# Sensor_Board.net
KiCad netlist of a schematic drawn in Altium Designer
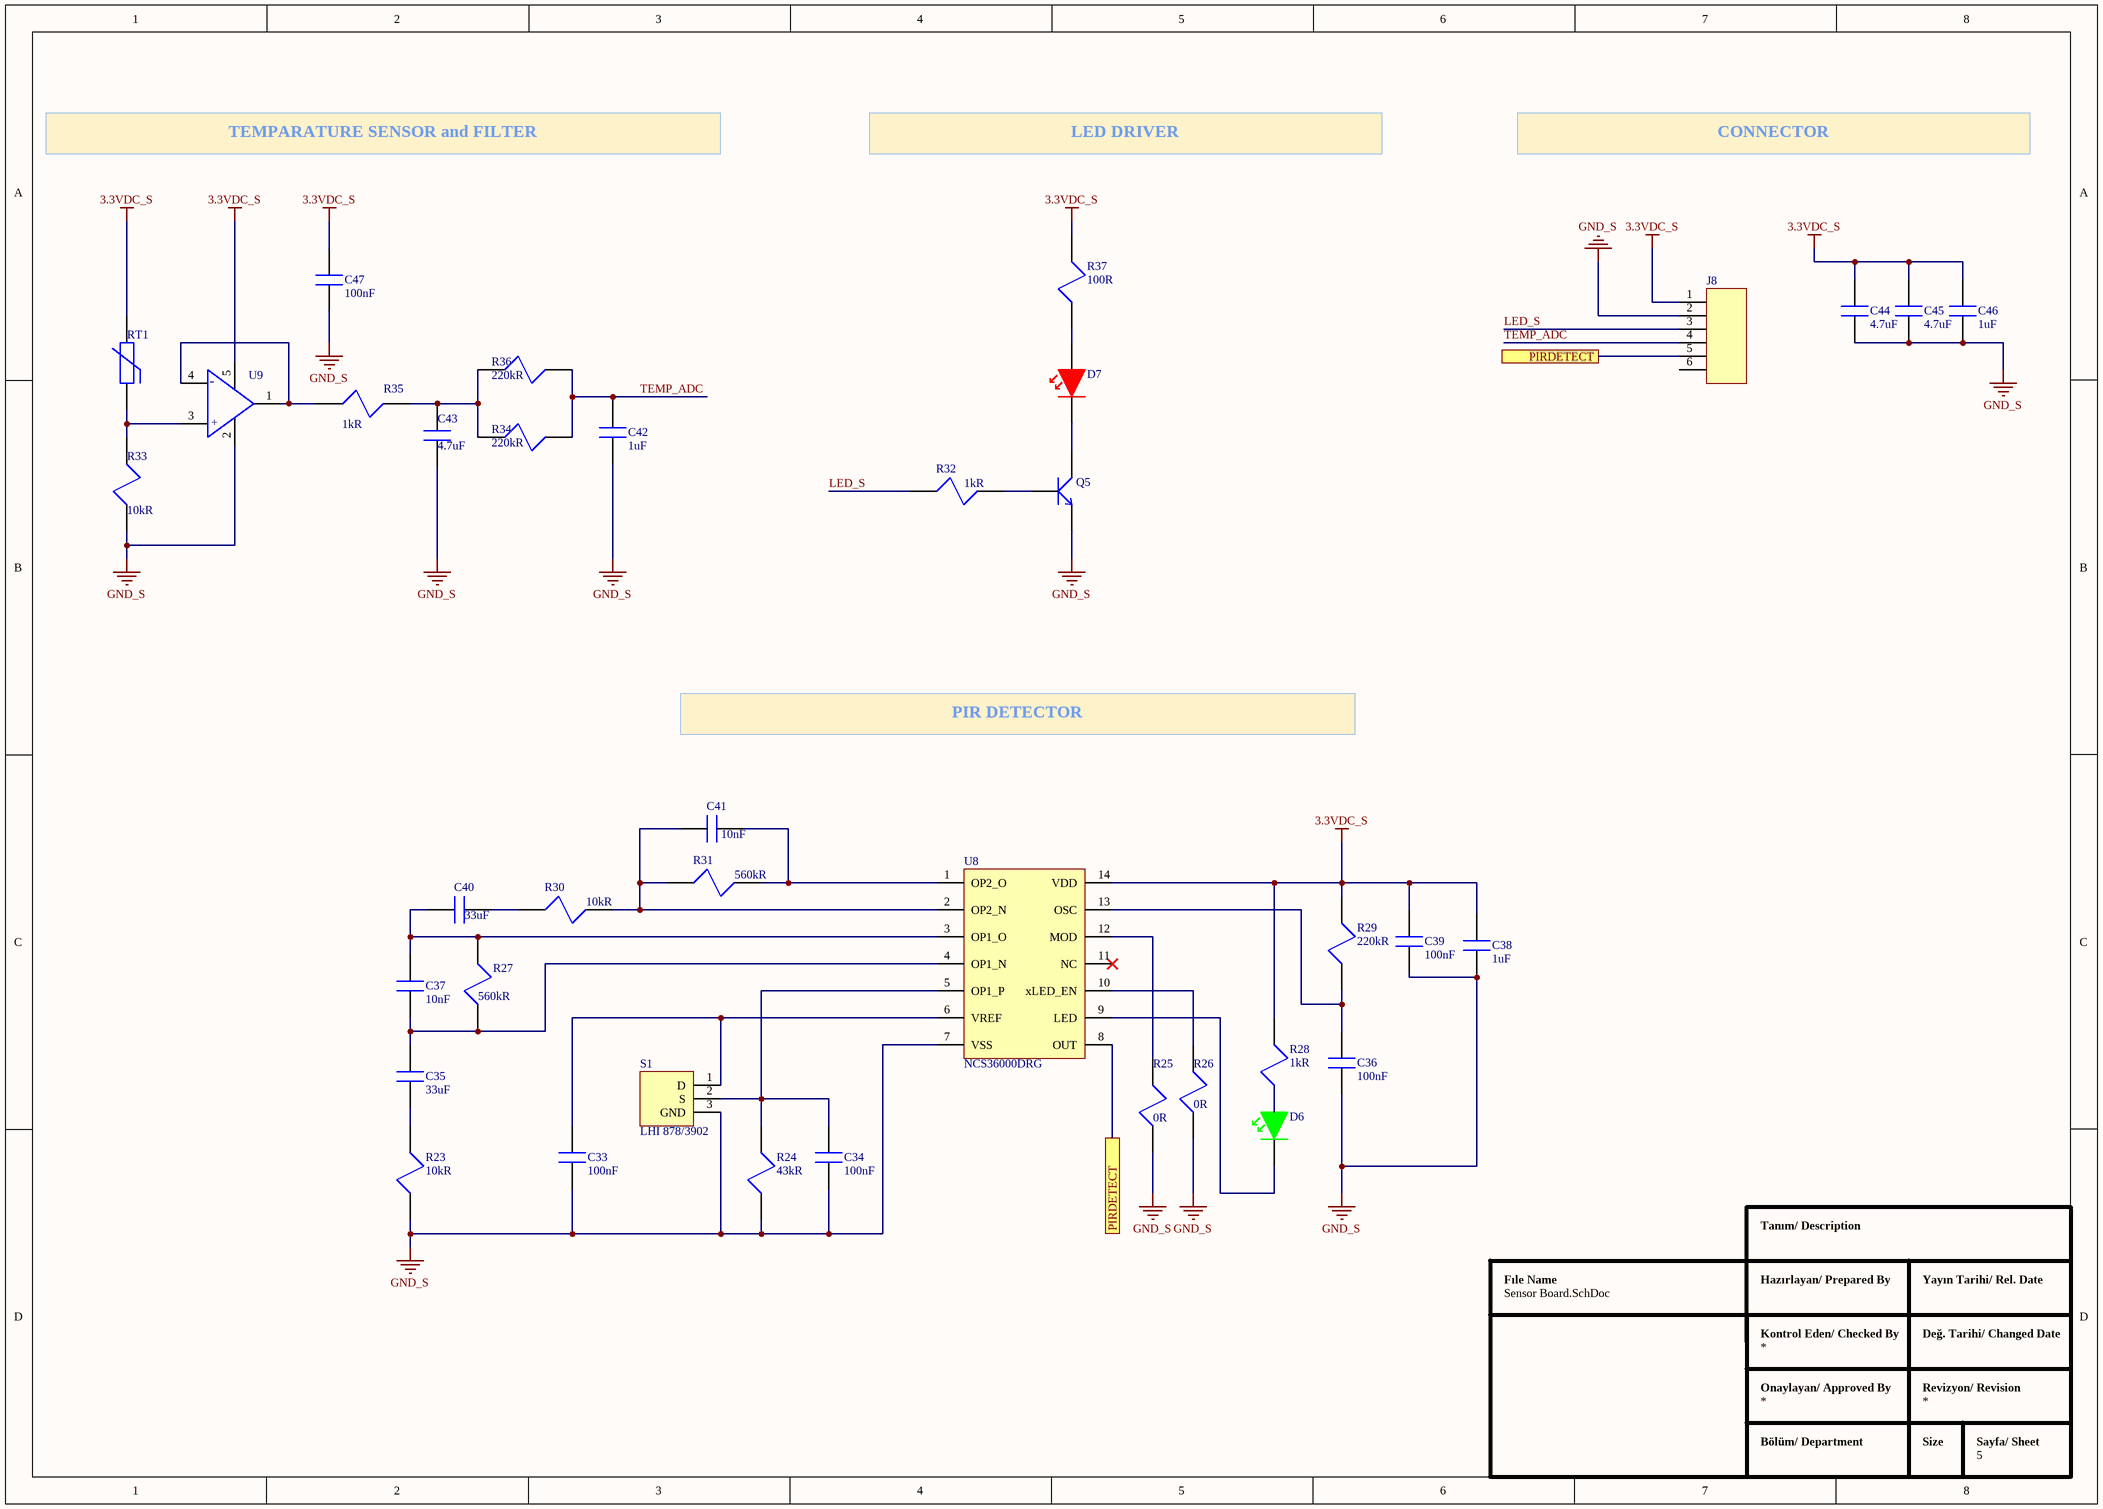
[diagram p0: Sensor Board.SchDoc]

(export (version "E")
  (design (tool "Eeschema 10.0.6"))
  (components
    (comp (ref "C33")
      (value "C0603C104M5RAC7867")
      (footprint "CAP_0603")
      (description "CAP CER 0.1UF 50V 20% X7R 0603")
      (fields
        (field (name "MANUFACTURER") "KEMET")
        (field (name "MANUFACTURER PART NUMBER") "C0603C104M5RACTU")
        (field (name "CAPACITANCE") "100nF")
        (field (name "DESIGNED BY") "Rumeysa Şahin")
      )
      (libsource (lib "Integrated_Library1") (part "CAP CER 100nF 0603"))
    )
    (comp (ref "C34")
      (value "C0603C104M5RAC7867")
      (footprint "CAP_0603")
      (description "CAP CER 0.1UF 50V 20% X7R 0603")
      (fields
        (field (name "MANUFACTURER") "KEMET")
        (field (name "MANUFACTURER PART NUMBER") "C0603C104M5RACTU")
        (field (name "CAPACITANCE") "100nF")
        (field (name "DESIGNED BY") "Rumeysa Şahin")
      )
      (libsource (lib "Integrated_Library1") (part "CAP CER 100nF 0603"))
    )
    (comp (ref "C35")
      (value "C3216X5R1E336M160AC")
      (footprint "CAP_1206")
      (description "C Series 1206 33 uF 25 V ±20 % Tolerance X5R SMT Multilayer Ceramic Capacitor")
      (fields
        (field (name "MANUFACTURER") "TDK")
        (field (name "TOLERANCE") "20%")
        (field (name "CAPACITANCE") "33uF")
        (field (name "DESIGNED BY") "Rumeysa Şahin")
      )
      (libsource (lib "Integrated_Library1") (part "CAP CER 33uF 1206"))
    )
    (comp (ref "C36")
      (value "C0603C104M5RAC7867")
      (footprint "CAP_0603")
      (description "CAP CER 0.1UF 50V 20% X7R 0603")
      (fields
        (field (name "MANUFACTURER") "KEMET")
        (field (name "MANUFACTURER PART NUMBER") "C0603C104M5RACTU")
        (field (name "CAPACITANCE") "100nF")
        (field (name "DESIGNED BY") "Rumeysa Şahin")
      )
      (libsource (lib "Integrated_Library1") (part "CAP CER 100nF 0603"))
    )
    (comp (ref "C37")
      (value "0603B103K160CT")
      (footprint "CAP_0603")
      (description "Multilayer Ceramic Capacitor, 0.01 F, 10%, X7R, 16 V, 0603 [1608 Metric] RoHS Compliant: Yes")
      (fields
        (field (name "MANUFACTURER") "Walsin Technologies")
        (field (name "TOLERANCE") "10%")
        (field (name "CAPACITANCE") "10nF")
        (field (name "DESIGNED BY") "Rumeysa Şahin")
      )
      (libsource (lib "Integrated_Library1") (part "CAP CER 10nF 0603"))
    )
    (comp (ref "C38")
      (value "CL21B105KBFNNNE")
      (footprint "CAP_0805")
      (description "CAP CER 1UF 50V X7R 0805")
      (fields
        (field (name "MANUFACTURER") "Samsung")
        (field (name "TOLERANCE") "10%")
        (field (name "CAPACITANCE") "1uF")
        (field (name "DESIGNED BY") "Rumeysa Şahin")
      )
      (libsource (lib "Integrated_Library1") (part "CAP CER 1UF 0805"))
    )
    (comp (ref "C39")
      (value "C0603C104M5RAC7867")
      (footprint "CAP_0603")
      (description "CAP CER 0.1UF 50V 20% X7R 0603")
      (fields
        (field (name "MANUFACTURER") "KEMET")
        (field (name "MANUFACTURER PART NUMBER") "C0603C104M5RACTU")
        (field (name "CAPACITANCE") "100nF")
        (field (name "DESIGNED BY") "Rumeysa Şahin")
      )
      (libsource (lib "Integrated_Library1") (part "CAP CER 100nF 0603"))
    )
    (comp (ref "C40")
      (value "C3216X5R1E336M160AC")
      (footprint "CAP_1206")
      (description "C Series 1206 33 uF 25 V ±20 % Tolerance X5R SMT Multilayer Ceramic Capacitor")
      (fields
        (field (name "MANUFACTURER") "TDK")
        (field (name "TOLERANCE") "20%")
        (field (name "CAPACITANCE") "33uF")
        (field (name "DESIGNED BY") "Rumeysa Şahin")
      )
      (libsource (lib "Integrated_Library1") (part "CAP CER 33uF 1206"))
    )
    (comp (ref "C41")
      (value "0603B103K160CT")
      (footprint "CAP_0603")
      (description "Multilayer Ceramic Capacitor, 0.01 F, 10%, X7R, 16 V, 0603 [1608 Metric] RoHS Compliant: Yes")
      (fields
        (field (name "MANUFACTURER") "Walsin Technologies")
        (field (name "TOLERANCE") "10%")
        (field (name "CAPACITANCE") "10nF")
        (field (name "DESIGNED BY") "Rumeysa Şahin")
      )
      (libsource (lib "Integrated_Library1") (part "CAP CER 10nF 0603"))
    )
    (comp (ref "C42")
      (value "CL21B105KBFNNNE")
      (footprint "CAP_0805")
      (description "CAP CER 1UF 50V X7R 0805")
      (fields
        (field (name "MANUFACTURER") "Samsung")
        (field (name "TOLERANCE") "10%")
        (field (name "CAPACITANCE") "1uF")
        (field (name "DESIGNED BY") "Rumeysa Şahin")
      )
      (libsource (lib "Integrated_Library1") (part "CAP CER 1UF 0805"))
    )
    (comp (ref "C43")
      (value "CL21A475KAQNNNE")
      (footprint "CAP_0805")
      (description "CAP CER 4.7UF 25V X5R 0805")
      (fields
        (field (name "MANUFACTURER") "Samsung")
        (field (name "TOLERANCE") "10%")
        (field (name "CAPACITANCE") "4.7uF")
        (field (name "DESIGNED BY") "Rumeysa Şahin")
      )
      (libsource (lib "Integrated_Library1") (part "CAP CER 4.7uF 0805"))
    )
    (comp (ref "C44")
      (value "CL21A475KAQNNNE")
      (footprint "CAP_0805")
      (description "CAP CER 4.7UF 25V X5R 0805")
      (fields
        (field (name "MANUFACTURER") "Samsung")
        (field (name "TOLERANCE") "10%")
        (field (name "CAPACITANCE") "4.7uF")
        (field (name "DESIGNED BY") "Rumeysa Şahin")
      )
      (libsource (lib "Integrated_Library1") (part "CAP CER 4.7uF 0805"))
    )
    (comp (ref "C45")
      (value "CL21A475KAQNNNE")
      (footprint "CAP_0805")
      (description "CAP CER 4.7UF 25V X5R 0805")
      (fields
        (field (name "MANUFACTURER") "Samsung")
        (field (name "TOLERANCE") "10%")
        (field (name "CAPACITANCE") "4.7uF")
        (field (name "DESIGNED BY") "Rumeysa Şahin")
      )
      (libsource (lib "Integrated_Library1") (part "CAP CER 4.7uF 0805"))
    )
    (comp (ref "C46")
      (value "CL21B105KBFNNNE")
      (footprint "CAP_0805")
      (description "CAP CER 1UF 50V X7R 0805")
      (fields
        (field (name "MANUFACTURER") "Samsung")
        (field (name "TOLERANCE") "10%")
        (field (name "CAPACITANCE") "1uF")
        (field (name "DESIGNED BY") "Rumeysa Şahin")
      )
      (libsource (lib "Integrated_Library1") (part "CAP CER 1UF 0805"))
    )
    (comp (ref "C47")
      (value "C0603C104M5RAC7867")
      (footprint "CAP_0603")
      (description "CAP CER 0.1UF 50V 20% X7R 0603")
      (fields
        (field (name "MANUFACTURER") "KEMET")
        (field (name "MANUFACTURER PART NUMBER") "C0603C104M5RACTU")
        (field (name "CAPACITANCE") "100nF")
        (field (name "DESIGNED BY") "Rumeysa Şahin")
      )
      (libsource (lib "Integrated_Library1") (part "CAP CER 100nF 0603"))
    )
    (comp (ref "D6")
      (value "LTST-C171GKT")
      (footprint "LED_GREEN_0805")
      (description "Green 569nm LED Indication - Discrete 2.1V 0805 (2012 Metric)")
      (fields
        (field (name "MANUFACTURER") "Osram Opto")
        (field (name "MANUFACTURER PART NUMBER") "LH R974-LP-1")
        (field (name "DESIGNED BY") "Rumeysa Şahin")
      )
      (libsource (lib "Integrated_Library1") (part "LED GREEN 0805"))
    )
    (comp (ref "D7")
      (value "LH R974-LP-1")
      (footprint "LED_RED_0805")
      (description "LED Uni-Color Hyper Red 660nm 2-Pin Chip 0805(2012Metric) T/R")
      (fields (field (name "MANUFACTURER") "Osram Opto") (field (name "DESIGNED BY") "Rumeysa Şahin"))
      (libsource (lib "Integrated_Library1") (part "LED RED 0805"))
    )
    (comp (ref "J8")
      (value "64800611622")
      (footprint "64800611622")
      (description "Conn, Header, 6POS, 1ROW, 1.5MM;")
      (fields (field (name "MANUFACTURER") "Wurth Electronics") (field (name "DESIGNED BY") "Rumeysa Şahin"))
      (libsource (lib "Integrated_Library1") (part "64800611622_CONN_6PIN"))
    )
    (comp (ref "Q5")
      (value "MMBT3904-7-F")
      (footprint "SOT23F")
      (description "NPN Ic=200mA Vceo=40V hfe=100~300 fT=310MHz P=300mW SOT-23")
      (fields (field (name "MANUFACTURER") "Diodes Zetex") (field (name "DESIGNED BY") "Rumeysa Şahin"))
      (libsource (lib "Integrated_Library1") (part "MMBT3904-7-F"))
    )
    (comp (ref "R23")
      (value "RC0603DR-0710KL")
      (footprint "RES_0603")
      (description "Res Thick Film 0603 10K Ohm 0.5% 1/10W ±100ppm/°C Molded SMD Paper T/R")
      (fields
        (field (name "MANUFACTURER") "Yageo")
        (field (name "TOLERANCE") "0.5%")
        (field (name "RESISTANCE") "10kR")
        (field (name "DESIGNED BY") "Rumeysa Şahin")
      )
      (libsource (lib "Integrated_Library1") (part "RES 10K OHM 0603"))
    )
    (comp (ref "R24")
      (value "RC0603JR-0743KL")
      (footprint "RES_0603")
      (description "Res Thick Film 0603 43K Ohm 5% 0.1W(1/10W) ±100ppm/°C Pad SMD T/R")
      (fields
        (field (name "MANUFACTURER") "Yageo")
        (field (name "TOLERANCE") "5%")
        (field (name "RESISTANCE") "43kR")
        (field (name "DESIGNED BY") "Rumeysa Şahin")
      )
      (libsource (lib "Integrated_Library1") (part "RES 43K OHM 0603"))
    )
    (comp (ref "R25")
      (value "RC0603JR-070RL")
      (footprint "RES_0603")
      (description "RES SMD 0 OHM JUMPER 1/10W 0603")
      (fields
        (field (name "MANUFACTURER") "Yageo")
        (field (name "TOLERANCE") "1%")
        (field (name "RESISTANCE") "0R")
        (field (name "DESIGNED BY") "Rumeysa Şahin")
      )
      (libsource (lib "Integrated_Library1") (part "RES 0 OHM 0603"))
    )
    (comp (ref "R26")
      (value "RC0603JR-070RL")
      (footprint "RES_0603")
      (description "RES SMD 0 OHM JUMPER 1/10W 0603")
      (fields
        (field (name "MANUFACTURER") "Yageo")
        (field (name "TOLERANCE") "1%")
        (field (name "RESISTANCE") "0R")
        (field (name "DESIGNED BY") "Rumeysa Şahin")
      )
      (libsource (lib "Integrated_Library1") (part "RES 0 OHM 0603"))
    )
    (comp (ref "R27")
      (value "RC0603JR-07560KL")
      (footprint "RES_0603")
      (description "Res Thick Film 0603 560K Ohm 5% 0.1W(1/10W) ±100ppm/C Molded SMD Paper T/R")
      (fields
        (field (name "MANUFACTURER") "Yageo")
        (field (name "TOLERANCE") "5%")
        (field (name "RESISTANCE") "560kR")
        (field (name "DESIGNED BY") "Rumeysa Şahin")
      )
      (libsource (lib "Integrated_Library1") (part "RES 560K OHM 0603"))
    )
    (comp (ref "R28")
      (value "RC0603FR-071KL")
      (footprint "RES_0603")
      (description "Res Thick Film 0603 1K Ohm 1% 1/10W ±100ppm/°C Molded SMD SMD Paper T/R")
      (fields
        (field (name "MANUFACTURER") "Yageo")
        (field (name "TOLERANCE") "1%")
        (field (name "RESISTANCE") "1kR")
        (field (name "DESIGNED BY") "Rumeysa Şahin")
      )
      (libsource (lib "Integrated_Library1") (part "RES 1K OHM 0603"))
    )
    (comp (ref "R29")
      (value "RC0603JR-07220KL")
      (footprint "RES_0603")
      (description "Res Thick Film 0603 220K Ohm 5% 0.1W(1/10W) ±100ppm/C Pad SMD T/R")
      (fields
        (field (name "MANUFACTURER") "Yageo")
        (field (name "TOLERANCE") "5%")
        (field (name "RESISTANCE") "220kR")
        (field (name "DESIGNED BY") "Rumeysa Şahin")
      )
      (libsource (lib "Integrated_Library1") (part "RES 220K OHM 0603"))
    )
    (comp (ref "R30")
      (value "RC0603DR-0710KL")
      (footprint "RES_0603")
      (description "Res Thick Film 0603 10K Ohm 0.5% 1/10W ±100ppm/°C Molded SMD Paper T/R")
      (fields
        (field (name "MANUFACTURER") "Yageo")
        (field (name "TOLERANCE") "0.5%")
        (field (name "RESISTANCE") "10kR")
        (field (name "DESIGNED BY") "Rumeysa Şahin")
      )
      (libsource (lib "Integrated_Library1") (part "RES 10K OHM 0603"))
    )
    (comp (ref "R31")
      (value "RC0603JR-07560KL")
      (footprint "RES_0603")
      (description "Res Thick Film 0603 560K Ohm 5% 0.1W(1/10W) ±100ppm/C Molded SMD Paper T/R")
      (fields
        (field (name "MANUFACTURER") "Yageo")
        (field (name "TOLERANCE") "5%")
        (field (name "RESISTANCE") "560kR")
        (field (name "DESIGNED BY") "Rumeysa Şahin")
      )
      (libsource (lib "Integrated_Library1") (part "RES 560K OHM 0603"))
    )
    (comp (ref "R32")
      (value "RC0603FR-071KL")
      (footprint "RES_0603")
      (description "Res Thick Film 0603 1K Ohm 1% 1/10W ±100ppm/°C Molded SMD SMD Paper T/R")
      (fields
        (field (name "MANUFACTURER") "Yageo")
        (field (name "TOLERANCE") "1%")
        (field (name "RESISTANCE") "1kR")
        (field (name "DESIGNED BY") "Rumeysa Şahin")
      )
      (libsource (lib "Integrated_Library1") (part "RES 1K OHM 0603"))
    )
    (comp (ref "R33")
      (value "RC0603DR-0710KL")
      (footprint "RES_0603")
      (description "Res Thick Film 0603 10K Ohm 0.5% 1/10W ±100ppm/°C Molded SMD Paper T/R")
      (fields
        (field (name "MANUFACTURER") "Yageo")
        (field (name "TOLERANCE") "0.5%")
        (field (name "RESISTANCE") "10kR")
        (field (name "DESIGNED BY") "Rumeysa Şahin")
      )
      (libsource (lib "Integrated_Library1") (part "RES 10K OHM 0603"))
    )
    (comp (ref "R34")
      (value "RC0603JR-07220KL")
      (footprint "RES_0603")
      (description "Res Thick Film 0603 220K Ohm 5% 0.1W(1/10W) ±100ppm/C Pad SMD T/R")
      (fields
        (field (name "MANUFACTURER") "Yageo")
        (field (name "TOLERANCE") "5%")
        (field (name "RESISTANCE") "220kR")
        (field (name "DESIGNED BY") "Rumeysa Şahin")
      )
      (libsource (lib "Integrated_Library1") (part "RES 220K OHM 0603"))
    )
    (comp (ref "R35")
      (value "RC0603FR-071KL")
      (footprint "RES_0603")
      (description "Res Thick Film 0603 1K Ohm 1% 1/10W ±100ppm/°C Molded SMD SMD Paper T/R")
      (fields
        (field (name "MANUFACTURER") "Yageo")
        (field (name "TOLERANCE") "1%")
        (field (name "RESISTANCE") "1kR")
        (field (name "DESIGNED BY") "Rumeysa Şahin")
      )
      (libsource (lib "Integrated_Library1") (part "RES 1K OHM 0603"))
    )
    (comp (ref "R36")
      (value "RC0603JR-07220KL")
      (footprint "RES_0603")
      (description "Res Thick Film 0603 220K Ohm 5% 0.1W(1/10W) ±100ppm/C Pad SMD T/R")
      (fields
        (field (name "MANUFACTURER") "Yageo")
        (field (name "TOLERANCE") "5%")
        (field (name "RESISTANCE") "220kR")
        (field (name "DESIGNED BY") "Rumeysa Şahin")
      )
      (libsource (lib "Integrated_Library1") (part "RES 220K OHM 0603"))
    )
    (comp (ref "R37")
      (value "RC0603JR-13100RL")
      (footprint "RES_0603")
      (description "Res Thick Film 0603 100 Ohm 5% 0.1W(1/10W) ±100ppm/C Pad SMD T/R")
      (fields
        (field (name "MANUFACTURER") "Yageo")
        (field (name "TOLERANCE") "5%")
        (field (name "RESISTANCE") "100R")
        (field (name "DESIGNED BY") "Rumeysa Şahin")
      )
      (libsource (lib "Integrated_Library1") (part "RES 100 OHM 0603"))
    )
    (comp (ref "RT1")
      (value "TFPT1206L1002FM")
      (footprint "TFPT1206L1002FM")
      (description "Thermistor PTC 10K Ohm 1% 2-Pin 1206 Surface Mount Solder Pad T/R Automotive")
      (fields
        (field (name "MANUFACTURER") "Vishay Dale")
        (field (name "TOLERANCE") "1%")
        (field (name "DESIGNED BY") "Rumeysa Şahin")
      )
      (libsource (lib "Integrated_Library1") (part "TFPT1206L1002FM"))
    )
    (comp (ref "S1")
      (value "LHI 878/3902")
      (footprint "LHI 878/3902")
      (description "Pyro Detector Dual, Motion Sens")
      (fields
        (field (name "MANUFACTURER") "Excelitas")
        (field (name "MANUFACTURER PART NUMBER") "PYD1388/7083")
        (field (name "DESIGNED BY") "Rumeysa Şahin")
      )
      (libsource (lib "Integrated_Library1") (part "LHI 878/3902"))
    )
    (comp (ref "U8")
      (value "NCS36000DRG")
      (footprint "SOIC14")
      (description "NCS36000 Series Single 5.75V Passive Infrared Detector Controller (PIR) -SOIC-14")
      (fields (field (name "MANUFACTURER") "ON Semiconductor") (field (name "DESIGNED BY") "Rumeysa Şahin"))
      (libsource (lib "Integrated_Library1") (part "NCS36000"))
    )
    (comp (ref "U9")
      (value "OPA314AIDBVR")
      (footprint "SOT23-5")
      (description "IC OPAMP GP 3MHZ RRO SOT23-5")
      (fields (field (name "MANUFACTURER") "Texas Instruments") (field (name "DESIGNED BY") "Ruemysa Şahin"))
      (libsource (lib "Integrated_Library1") (part "OPA314"))
    )
  )
  (nets
    (net (code "1") (name "/LED_S") (class "Default")
      (node (ref "J8") (pin "3") (pintype "power_in"))
      (node (ref "R32") (pin "1") (pintype "passive"))
    )
    (net (code "2") (name "/PIRDETECT") (class "Default")
      (node (ref "J8") (pin "5") (pintype "power_in"))
      (node (ref "U8") (pin "8") (pinfunction "OUT_8") (pintype "passive"))
    )
    (net (code "3") (name "/TEMP_ADC") (class "Default")
      (node (ref "C42") (pin "2") (pinfunction "2_2") (pintype "passive"))
      (node (ref "J8") (pin "4") (pintype "power_in"))
      (node (ref "R34") (pin "2") (pinfunction "2_2") (pintype "passive"))
      (node (ref "R36") (pin "2") (pinfunction "2_2") (pintype "passive"))
    )
    (net (code "4") (name "3.3VDC_S") (class "Default")
      (node (ref "C38") (pin "2") (pinfunction "2_2") (pintype "passive"))
      (node (ref "C39") (pin "2") (pinfunction "2_2") (pintype "passive"))
      (node (ref "C44") (pin "2") (pinfunction "2_2") (pintype "passive"))
      (node (ref "C45") (pin "2") (pinfunction "2_2") (pintype "passive"))
      (node (ref "C46") (pin "2") (pinfunction "2_2") (pintype "passive"))
      (node (ref "C47") (pin "2") (pinfunction "2_2") (pintype "passive"))
      (node (ref "J8") (pin "1") (pintype "power_in"))
      (node (ref "R28") (pin "2") (pinfunction "2_2") (pintype "passive"))
      (node (ref "R29") (pin "2") (pinfunction "2_2") (pintype "passive"))
      (node (ref "R37") (pin "2") (pinfunction "2_2") (pintype "passive"))
      (node (ref "RT1") (pin "2") (pinfunction "2_2") (pintype "passive"))
      (node (ref "U8") (pin "14") (pinfunction "VDD_14") (pintype "passive"))
      (node (ref "U9") (pin "5") (pinfunction "5_5") (pintype "passive"))
    )
    (net (code "5") (name "GND_S") (class "Default")
      (node (ref "C33") (pin "1") (pinfunction "1_1") (pintype "passive"))
      (node (ref "C34") (pin "1") (pinfunction "1_1") (pintype "passive"))
      (node (ref "C36") (pin "1") (pinfunction "1_1") (pintype "passive"))
      (node (ref "C38") (pin "1") (pinfunction "1_1") (pintype "passive"))
      (node (ref "C39") (pin "1") (pinfunction "1_1") (pintype "passive"))
      (node (ref "C42") (pin "1") (pinfunction "1_1") (pintype "passive"))
      (node (ref "C43") (pin "1") (pinfunction "1_1") (pintype "passive"))
      (node (ref "C44") (pin "1") (pinfunction "1_1") (pintype "passive"))
      (node (ref "C45") (pin "1") (pinfunction "1_1") (pintype "passive"))
      (node (ref "C46") (pin "1") (pinfunction "1_1") (pintype "passive"))
      (node (ref "C47") (pin "1") (pinfunction "1_1") (pintype "passive"))
      (node (ref "J8") (pin "2") (pintype "power_in"))
      (node (ref "Q5") (pin "2") (pinfunction "E_2") (pintype "power_in"))
      (node (ref "R23") (pin "1") (pintype "passive"))
      (node (ref "R24") (pin "1") (pintype "passive"))
      (node (ref "R25") (pin "1") (pintype "passive"))
      (node (ref "R26") (pin "1") (pintype "passive"))
      (node (ref "R33") (pin "2") (pinfunction "2_2") (pintype "passive"))
      (node (ref "S1") (pin "3") (pinfunction "GND_3") (pintype "passive"))
      (node (ref "U8") (pin "7") (pinfunction "VSS_7") (pintype "passive"))
      (node (ref "U9") (pin "2") (pinfunction "2_2") (pintype "passive"))
    )
    (net (code "6") (name "Net-(C35-Pad1)") (class "Default")
      (node (ref "C35") (pin "1") (pinfunction "1_1") (pintype "passive"))
      (node (ref "R23") (pin "2") (pinfunction "2_2") (pintype "passive"))
    )
    (net (code "7") (name "Net-(C40-Pad2)") (class "Default")
      (node (ref "C40") (pin "2") (pinfunction "2_2") (pintype "passive"))
      (node (ref "R30") (pin "1") (pintype "passive"))
    )
    (net (code "8") (name "Net-(C43-Pad2)") (class "Default")
      (node (ref "C43") (pin "2") (pinfunction "2_2") (pintype "passive"))
      (node (ref "R34") (pin "1") (pintype "passive"))
      (node (ref "R35") (pin "1") (pintype "passive"))
      (node (ref "R36") (pin "1") (pintype "passive"))
    )
    (net (code "9") (name "Net-(D6-Pad2)") (class "Default")
      (node (ref "D6") (pin "2") (pinfunction "2_2") (pintype "power_in"))
      (node (ref "R28") (pin "1") (pintype "passive"))
    )
    (net (code "10") (name "Net-(D7-Pad2)") (class "Default")
      (node (ref "D7") (pin "2") (pinfunction "2_2") (pintype "power_in"))
      (node (ref "R37") (pin "1") (pintype "passive"))
    )
    (net (code "11") (name "Net-(Q5-B)") (class "Default")
      (node (ref "Q5") (pin "1") (pinfunction "B_1") (pintype "power_in"))
      (node (ref "R32") (pin "2") (pinfunction "2_2") (pintype "passive"))
    )
    (net (code "12") (name "Net-(Q5-C)") (class "Default")
      (node (ref "D7") (pin "1") (pinfunction "1_1") (pintype "power_in"))
      (node (ref "Q5") (pin "3") (pinfunction "C_3") (pintype "power_in"))
    )
    (net (code "13") (name "Net-(R33-Pad1)") (class "Default")
      (node (ref "R33") (pin "1") (pintype "passive"))
      (node (ref "RT1") (pin "1") (pinfunction "1_1") (pintype "passive"))
      (node (ref "U9") (pin "3") (pinfunction "3_3") (pintype "passive"))
    )
    (net (code "14") (name "Net-(R35-Pad2)") (class "Default")
      (node (ref "R35") (pin "2") (pinfunction "2_2") (pintype "passive"))
      (node (ref "U9") (pin "1") (pinfunction "1_1") (pintype "passive"))
      (node (ref "U9") (pin "4") (pinfunction "4_4") (pintype "passive"))
    )
    (net (code "15") (name "Net-(S1-D)") (class "Default")
      (node (ref "C33") (pin "2") (pinfunction "2_2") (pintype "passive"))
      (node (ref "S1") (pin "1") (pinfunction "D_1") (pintype "passive"))
      (node (ref "U8") (pin "6") (pinfunction "VREF_6") (pintype "passive"))
    )
    (net (code "16") (name "Net-(S1-S)") (class "Default")
      (node (ref "C34") (pin "2") (pinfunction "2_2") (pintype "passive"))
      (node (ref "R24") (pin "2") (pinfunction "2_2") (pintype "passive"))
      (node (ref "S1") (pin "2") (pinfunction "S_2") (pintype "passive"))
      (node (ref "U8") (pin "5") (pinfunction "OP1_P_5") (pintype "passive"))
    )
    (net (code "17") (name "Net-(U8-LED)") (class "Default")
      (node (ref "D6") (pin "1") (pinfunction "1_1") (pintype "power_in"))
      (node (ref "U8") (pin "9") (pinfunction "LED_9") (pintype "passive"))
    )
    (net (code "18") (name "Net-(U8-MOD)") (class "Default")
      (node (ref "R25") (pin "2") (pinfunction "2_2") (pintype "passive"))
      (node (ref "U8") (pin "12") (pinfunction "MOD_12") (pintype "passive"))
    )
    (net (code "19") (name "Net-(U8-OP1_N)") (class "Default")
      (node (ref "C35") (pin "2") (pinfunction "2_2") (pintype "passive"))
      (node (ref "C37") (pin "1") (pinfunction "1_1") (pintype "passive"))
      (node (ref "R27") (pin "1") (pintype "passive"))
      (node (ref "U8") (pin "4") (pinfunction "OP1_N_4") (pintype "passive"))
    )
    (net (code "20") (name "Net-(U8-OP1_O)") (class "Default")
      (node (ref "C37") (pin "2") (pinfunction "2_2") (pintype "passive"))
      (node (ref "C40") (pin "1") (pinfunction "1_1") (pintype "passive"))
      (node (ref "R27") (pin "2") (pinfunction "2_2") (pintype "passive"))
      (node (ref "U8") (pin "3") (pinfunction "OP1_O_3") (pintype "passive"))
    )
    (net (code "21") (name "Net-(U8-OP2_N)") (class "Default")
      (node (ref "C41") (pin "1") (pinfunction "1_1") (pintype "passive"))
      (node (ref "R30") (pin "2") (pinfunction "2_2") (pintype "passive"))
      (node (ref "R31") (pin "1") (pintype "passive"))
      (node (ref "U8") (pin "2") (pinfunction "OP2_N_2") (pintype "passive"))
    )
    (net (code "22") (name "Net-(U8-OP2_O)") (class "Default")
      (node (ref "C41") (pin "2") (pinfunction "2_2") (pintype "passive"))
      (node (ref "R31") (pin "2") (pinfunction "2_2") (pintype "passive"))
      (node (ref "U8") (pin "1") (pinfunction "OP2_O_1") (pintype "passive"))
    )
    (net (code "23") (name "Net-(U8-OSC)") (class "Default")
      (node (ref "C36") (pin "2") (pinfunction "2_2") (pintype "passive"))
      (node (ref "R29") (pin "1") (pintype "passive"))
      (node (ref "U8") (pin "13") (pinfunction "OSC_13") (pintype "passive"))
    )
    (net (code "24") (name "Net-(U8-xLED_EN)") (class "Default")
      (node (ref "R26") (pin "2") (pinfunction "2_2") (pintype "passive"))
      (node (ref "U8") (pin "10") (pinfunction "xLED_EN_10") (pintype "passive"))
    )
    (net (code "25") (name "unconnected-(J8-Pad6)") (class "Default")
      (node (ref "J8") (pin "6") (pintype "power_in"))
    )
    (net (code "26") (name "unconnected-(U8-NC-Pad11)") (class "Default")
      (node (ref "U8") (pin "11") (pinfunction "NC_11") (pintype "passive+no_connect"))
    )
  )
)
